# Eddy_ESC.net
KiCad netlist of a schematic drawn in EAGLE
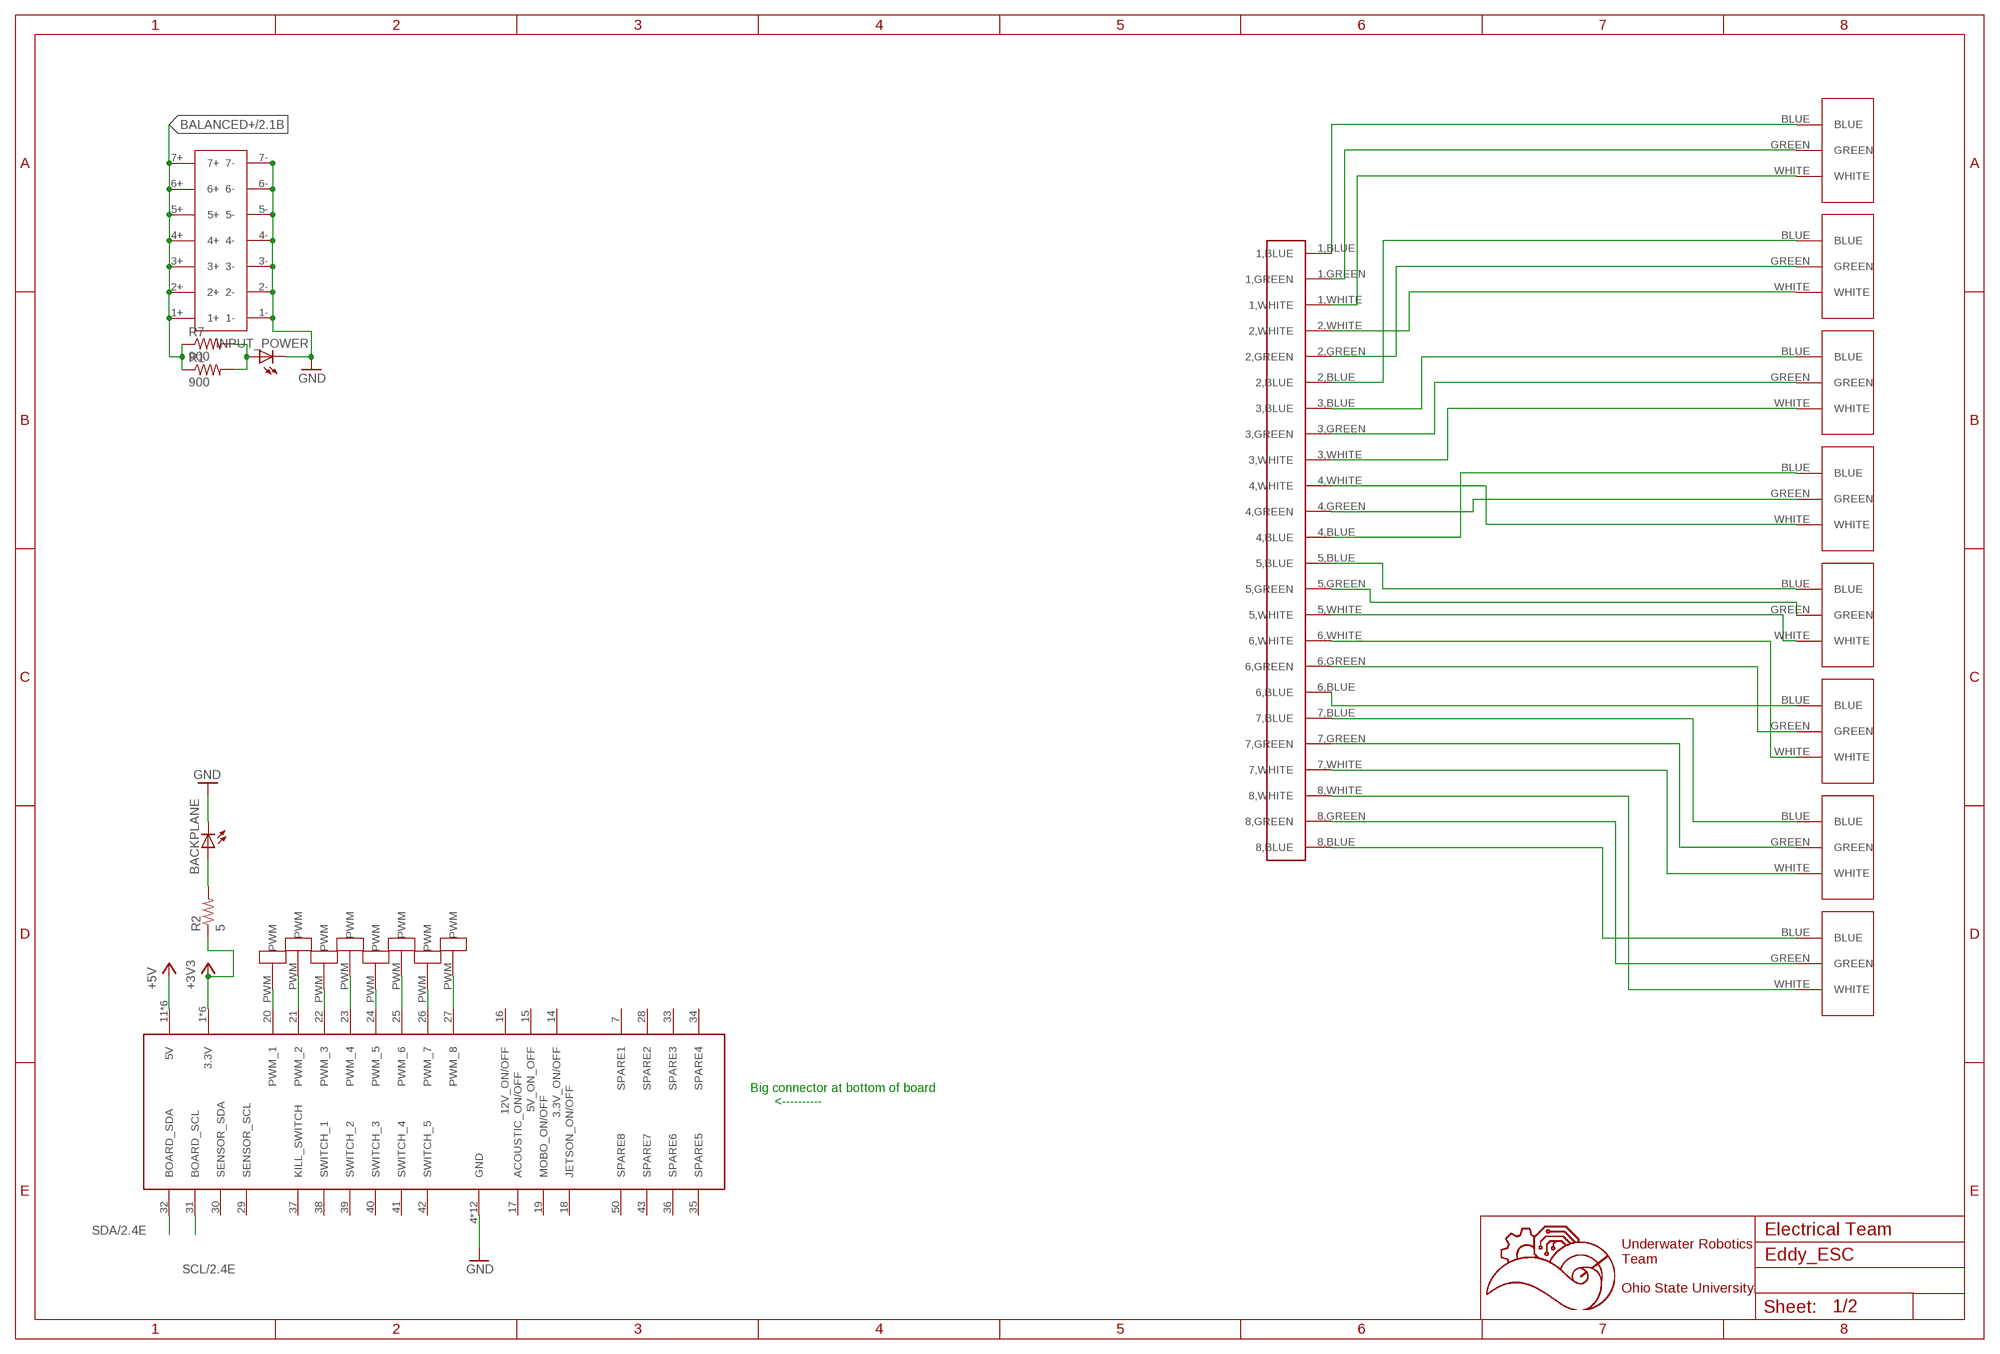
[diagram p0: schematic, sheet 1]
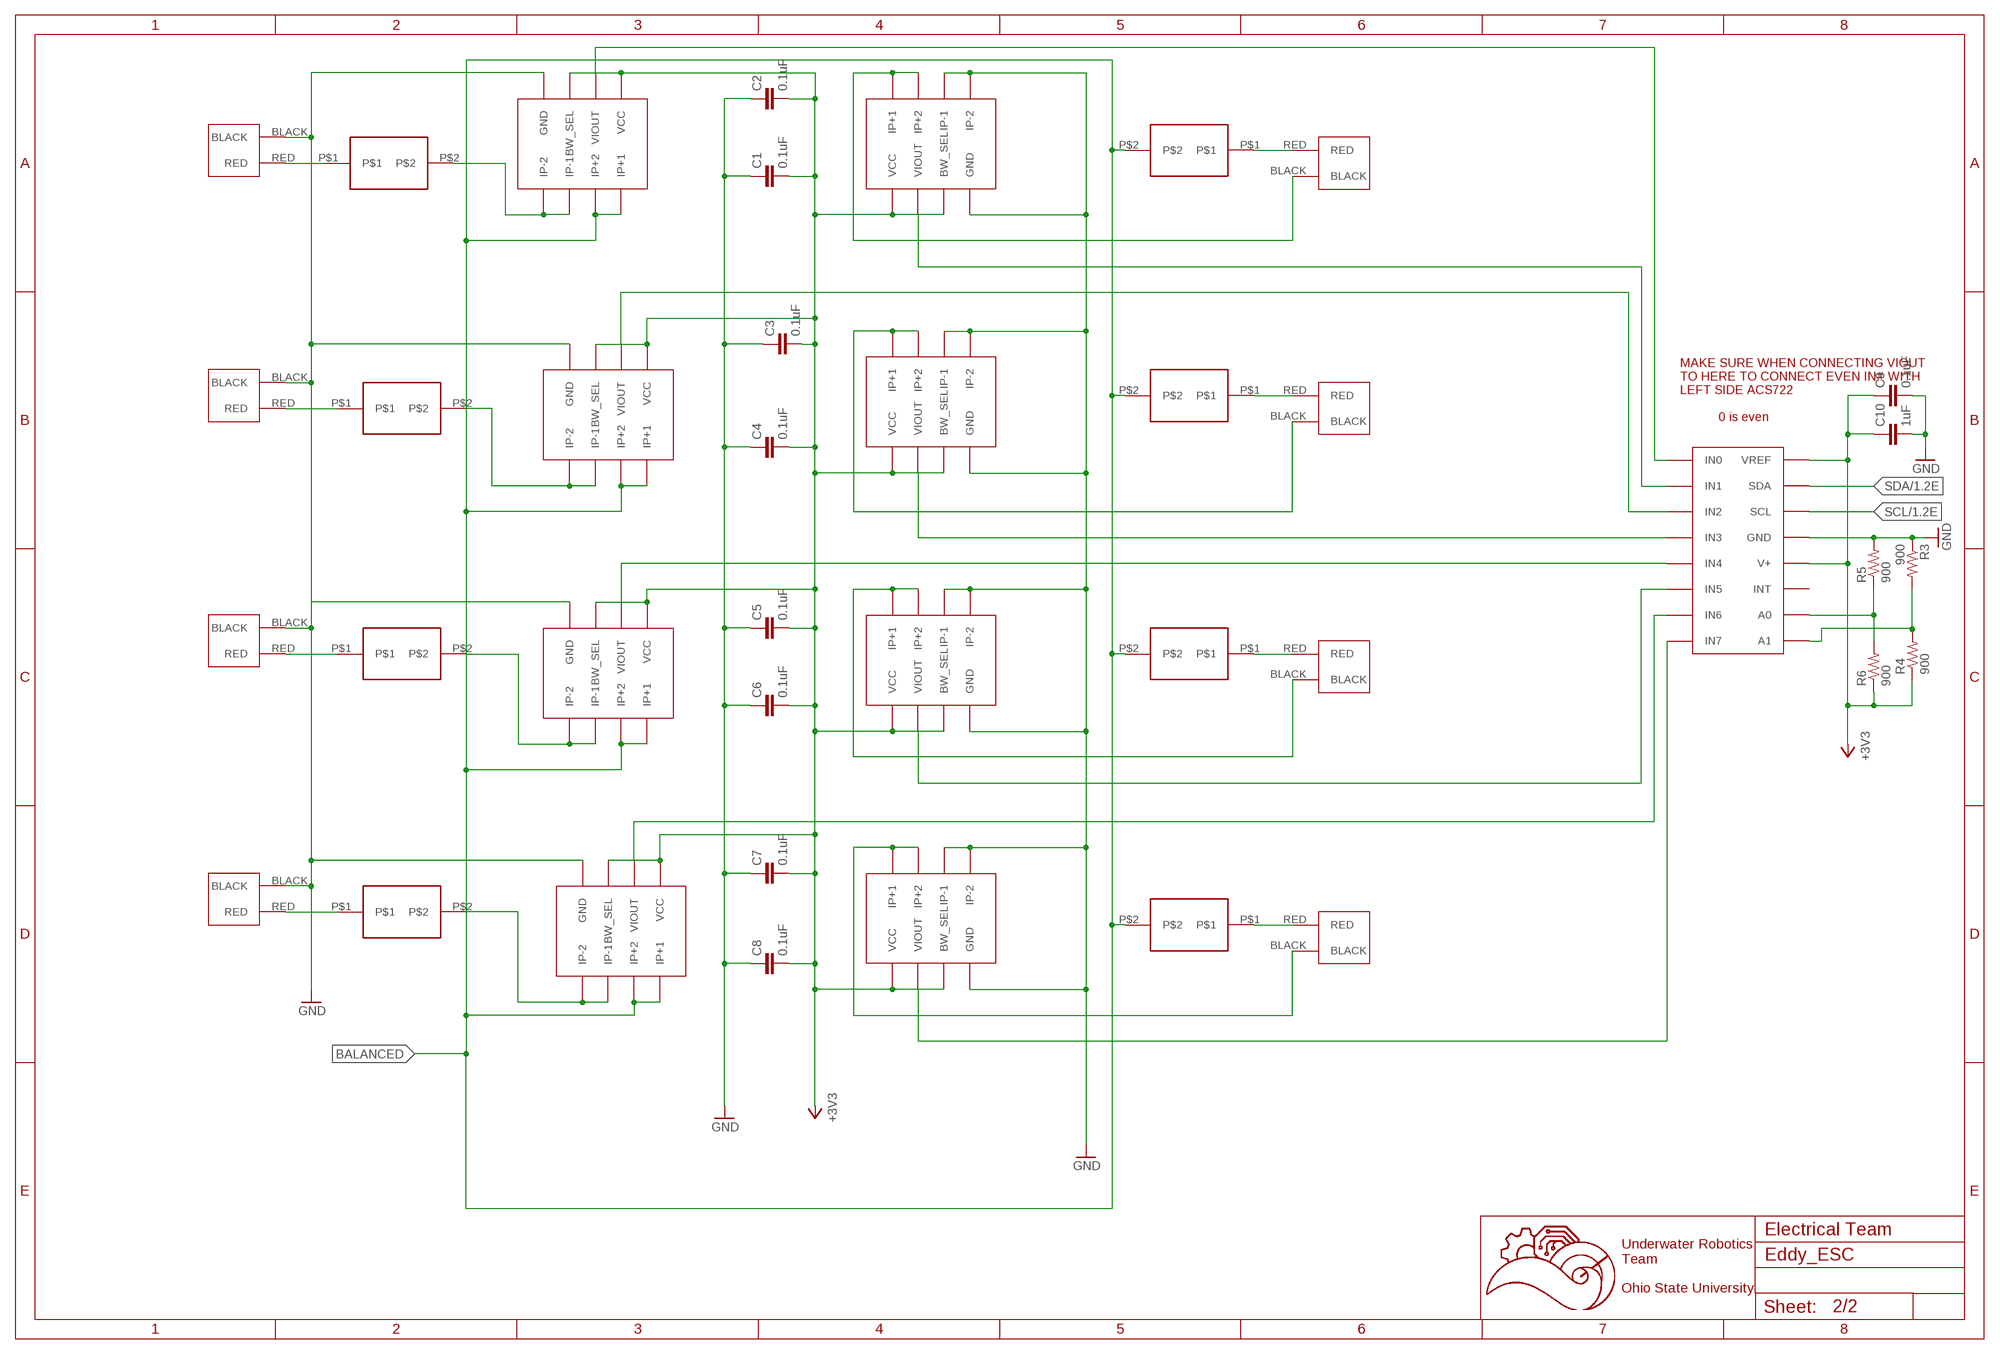
[diagram p1: schematic, sheet 2]

(export (version "E")
  (design (tool "Eeschema 10.0.6"))
  (components
    (comp (ref "C1")
      (value "0.1uF")
      (footprint "eagle-import:C0603")
      (libsource (lib "eagle-import") (part "C-EUC0603"))
    )
    (comp (ref "C2")
      (value "0.1uF")
      (footprint "eagle-import:C0603")
      (libsource (lib "eagle-import") (part "C-EUC0603"))
    )
    (comp (ref "C3")
      (value "0.1uF")
      (footprint "eagle-import:C0603")
      (libsource (lib "eagle-import") (part "C-EUC0603"))
    )
    (comp (ref "C4")
      (value "0.1uF")
      (footprint "eagle-import:C0603")
      (libsource (lib "eagle-import") (part "C-EUC0603"))
    )
    (comp (ref "C5")
      (value "0.1uF")
      (footprint "eagle-import:C0603")
      (libsource (lib "eagle-import") (part "C-EUC0603"))
    )
    (comp (ref "C6")
      (value "0.1uF")
      (footprint "eagle-import:C0603")
      (libsource (lib "eagle-import") (part "C-EUC0603"))
    )
    (comp (ref "C7")
      (value "0.1uF")
      (footprint "eagle-import:C0603")
      (libsource (lib "eagle-import") (part "C-EUC0603"))
    )
    (comp (ref "C8")
      (value "0.1uF")
      (footprint "eagle-import:C0603")
      (libsource (lib "eagle-import") (part "C-EUC0603"))
    )
    (comp (ref "C9")
      (value "0.1uF")
      (footprint "eagle-import:C0603")
      (libsource (lib "eagle-import") (part "C-EUC0603"))
    )
    (comp (ref "C10")
      (value "1uF")
      (footprint "eagle-import:C0603")
      (libsource (lib "eagle-import") (part "C-EUC0603"))
    )
    (comp (ref "R3")
      (value "900")
      (footprint "eagle-import:R0603")
      (libsource (lib "eagle-import") (part "R-US_R0603"))
    )
    (comp (ref "R4")
      (value "900")
      (footprint "eagle-import:R0603")
      (libsource (lib "eagle-import") (part "R-US_R0603"))
    )
    (comp (ref "R5")
      (value "900")
      (footprint "eagle-import:R0603")
      (libsource (lib "eagle-import") (part "R-US_R0603"))
    )
    (comp (ref "R6")
      (value "900")
      (footprint "eagle-import:R0603")
      (libsource (lib "eagle-import") (part "R-US_R0603"))
    )
    (comp (ref "U$20")
      (value "1711725")
      (footprint "eagle-import:1711725")
      (libsource (lib "eagle-import") (part "1711725"))
    )
    (comp (ref "U$21")
      (value "1711725")
      (footprint "eagle-import:1711725")
      (libsource (lib "eagle-import") (part "1711725"))
    )
    (comp (ref "U$22")
      (value "1711725")
      (footprint "eagle-import:1711725")
      (libsource (lib "eagle-import") (part "1711725"))
    )
    (comp (ref "U$23")
      (value "1711725")
      (footprint "eagle-import:1711725")
      (libsource (lib "eagle-import") (part "1711725"))
    )
    (comp (ref "U$24")
      (value "1711725")
      (footprint "eagle-import:1711725")
      (libsource (lib "eagle-import") (part "1711725"))
    )
    (comp (ref "U$25")
      (value "1711725")
      (footprint "eagle-import:1711725")
      (libsource (lib "eagle-import") (part "1711725"))
    )
    (comp (ref "U$26")
      (value "1711725")
      (footprint "eagle-import:1711725")
      (libsource (lib "eagle-import") (part "1711725"))
    )
    (comp (ref "U$27")
      (value "1711725")
      (footprint "eagle-import:1711725")
      (libsource (lib "eagle-import") (part "1711725"))
    )
    (comp (ref "U$28")
      (value "ACS722")
      (footprint "eagle-import:SOIC-8")
      (libsource (lib "eagle-import") (part "ACS722"))
    )
    (comp (ref "U$29")
      (value "ACS722")
      (footprint "eagle-import:SOIC-8")
      (libsource (lib "eagle-import") (part "ACS722"))
    )
    (comp (ref "U$30")
      (value "ACS722")
      (footprint "eagle-import:SOIC-8")
      (libsource (lib "eagle-import") (part "ACS722"))
    )
    (comp (ref "U$31")
      (value "ACS722")
      (footprint "eagle-import:SOIC-8")
      (libsource (lib "eagle-import") (part "ACS722"))
    )
    (comp (ref "U$32")
      (value "ACS722")
      (footprint "eagle-import:SOIC-8")
      (libsource (lib "eagle-import") (part "ACS722"))
    )
    (comp (ref "U$33")
      (value "ACS722")
      (footprint "eagle-import:SOIC-8")
      (libsource (lib "eagle-import") (part "ACS722"))
    )
    (comp (ref "U$34")
      (value "ACS722")
      (footprint "eagle-import:SOIC-8")
      (libsource (lib "eagle-import") (part "ACS722"))
    )
    (comp (ref "U$35")
      (value "ACS722")
      (footprint "eagle-import:SOIC-8")
      (libsource (lib "eagle-import") (part "ACS722"))
    )
    (comp (ref "U$36")
      (value "ADC128D818")
      (footprint "eagle-import:TSSOP-16")
      (libsource (lib "eagle-import") (part "ADC128D818"))
    )
    (comp (ref "U$37")
      (value "1206SFH")
      (footprint "eagle-import:1206SFH")
      (libsource (lib "eagle-import") (part "1206SFH"))
    )
    (comp (ref "U$38")
      (value "1206SFH")
      (footprint "eagle-import:1206SFH")
      (libsource (lib "eagle-import") (part "1206SFH"))
    )
    (comp (ref "U$39")
      (value "1206SFH")
      (footprint "eagle-import:1206SFH")
      (libsource (lib "eagle-import") (part "1206SFH"))
    )
    (comp (ref "U$40")
      (value "1206SFH")
      (footprint "eagle-import:1206SFH")
      (libsource (lib "eagle-import") (part "1206SFH"))
    )
    (comp (ref "U$41")
      (value "1206SFH")
      (footprint "eagle-import:1206SFH")
      (libsource (lib "eagle-import") (part "1206SFH"))
    )
    (comp (ref "U$42")
      (value "1206SFH")
      (footprint "eagle-import:1206SFH")
      (libsource (lib "eagle-import") (part "1206SFH"))
    )
    (comp (ref "U$43")
      (value "1206SFH")
      (footprint "eagle-import:1206SFH")
      (libsource (lib "eagle-import") (part "1206SFH"))
    )
    (comp (ref "U$44")
      (value "1206SFH")
      (footprint "eagle-import:1206SFH")
      (libsource (lib "eagle-import") (part "1206SFH"))
    )
    (comp (ref "BACKPLANE")
      (value "LEDCHIPLED_0603")
      (footprint "eagle-import:CHIPLED_0603")
      (libsource (lib "eagle-import") (part "LEDCHIPLED_0603"))
    )
    (comp (ref "INPUT_POWER")
      (value "LEDCHIPLED_0603")
      (footprint "eagle-import:CHIPLED_0603")
      (libsource (lib "eagle-import") (part "LEDCHIPLED_0603"))
    )
    (comp (ref "R1")
      (value "900")
      (footprint "eagle-import:R0603")
      (libsource (lib "eagle-import") (part "R-US_R0603"))
    )
    (comp (ref "R2")
      (value "5")
      (footprint "eagle-import:R0603")
      (libsource (lib "eagle-import") (part "R-US_R0603"))
    )
    (comp (ref "R7")
      (value "900")
      (footprint "eagle-import:R0603")
      (libsource (lib "eagle-import") (part "R-US_R0603"))
    )
    (comp (ref "U$1")
      (value "5530843-EDGE")
      (footprint "eagle-import:5530843-6-BOARDFINGERS")
      (libsource (lib "eagle-import") (part "5530843-EDGE"))
    )
    (comp (ref "U$2")
      (value "1711738")
      (footprint "eagle-import:1711738")
      (libsource (lib "eagle-import") (part "1711738"))
    )
    (comp (ref "U$3")
      (value "1711738")
      (footprint "eagle-import:1711738")
      (libsource (lib "eagle-import") (part "1711738"))
    )
    (comp (ref "U$4")
      (value "1711738")
      (footprint "eagle-import:1711738")
      (libsource (lib "eagle-import") (part "1711738"))
    )
    (comp (ref "U$5")
      (value "1711738")
      (footprint "eagle-import:1711738")
      (libsource (lib "eagle-import") (part "1711738"))
    )
    (comp (ref "U$6")
      (value "1711738")
      (footprint "eagle-import:1711738")
      (libsource (lib "eagle-import") (part "1711738"))
    )
    (comp (ref "U$7")
      (value "1711738")
      (footprint "eagle-import:1711738")
      (libsource (lib "eagle-import") (part "1711738"))
    )
    (comp (ref "U$8")
      (value "1711738")
      (footprint "eagle-import:1711738")
      (libsource (lib "eagle-import") (part "1711738"))
    )
    (comp (ref "U$9")
      (value "1711738")
      (footprint "eagle-import:1711738")
      (libsource (lib "eagle-import") (part "1711738"))
    )
    (comp (ref "U$10")
      (value "24PINCONVERTER")
      (footprint "eagle-import:24PINCONVERTER")
      (libsource (lib "eagle-import") (part "24PINCONVERTER"))
    )
    (comp (ref "U$11")
      (value "14PIN_VERT")
      (footprint "eagle-import:14PIN_VERT")
      (libsource (lib "eagle-import") (part "14PIN_VERT"))
    )
    (comp (ref "U$12")
      (value "MALE1PINHEADER")
      (footprint "eagle-import:MALE1PINHEADER")
      (libsource (lib "eagle-import") (part "MALE1PINHEADER"))
    )
    (comp (ref "U$13")
      (value "MALE1PINHEADER")
      (footprint "eagle-import:MALE1PINHEADER")
      (libsource (lib "eagle-import") (part "MALE1PINHEADER"))
    )
    (comp (ref "U$14")
      (value "MALE1PINHEADER")
      (footprint "eagle-import:MALE1PINHEADER")
      (libsource (lib "eagle-import") (part "MALE1PINHEADER"))
    )
    (comp (ref "U$15")
      (value "MALE1PINHEADER")
      (footprint "eagle-import:MALE1PINHEADER")
      (libsource (lib "eagle-import") (part "MALE1PINHEADER"))
    )
    (comp (ref "U$16")
      (value "MALE1PINHEADER")
      (footprint "eagle-import:MALE1PINHEADER")
      (libsource (lib "eagle-import") (part "MALE1PINHEADER"))
    )
    (comp (ref "U$17")
      (value "MALE1PINHEADER")
      (footprint "eagle-import:MALE1PINHEADER")
      (libsource (lib "eagle-import") (part "MALE1PINHEADER"))
    )
    (comp (ref "U$18")
      (value "MALE1PINHEADER")
      (footprint "eagle-import:MALE1PINHEADER")
      (libsource (lib "eagle-import") (part "MALE1PINHEADER"))
    )
    (comp (ref "U$19")
      (value "MALE1PINHEADER")
      (footprint "eagle-import:MALE1PINHEADER")
      (libsource (lib "eagle-import") (part "MALE1PINHEADER"))
    )
  )
  (nets
    (net (code "1") (name "+3V3") (class "Default")
      (node (ref "C1") (pin "2") (pinfunction "2_2") (pintype "passive"))
      (node (ref "C10") (pin "1") (pinfunction "1_1") (pintype "passive"))
      (node (ref "C2") (pin "2") (pinfunction "2_2") (pintype "passive"))
      (node (ref "C3") (pin "2") (pinfunction "2_2") (pintype "passive"))
      (node (ref "C4") (pin "2") (pinfunction "2_2") (pintype "passive"))
      (node (ref "C5") (pin "2") (pinfunction "2_2") (pintype "passive"))
      (node (ref "C6") (pin "2") (pinfunction "2_2") (pintype "passive"))
      (node (ref "C7") (pin "2") (pinfunction "2_2") (pintype "passive"))
      (node (ref "C8") (pin "2") (pinfunction "2_2") (pintype "passive"))
      (node (ref "C9") (pin "1") (pinfunction "1_1") (pintype "passive"))
      (node (ref "R2") (pin "1") (pinfunction "1_1") (pintype "passive"))
      (node (ref "R4") (pin "1") (pinfunction "1_1") (pintype "passive"))
      (node (ref "R6") (pin "1") (pinfunction "1_1") (pintype "passive"))
      (node (ref "U$1") (pin "1") (pinfunction "3.3V_1") (pintype "bidirectional"))
      (node (ref "U$1") (pin "2") (pinfunction "3.3V_2") (pintype "bidirectional"))
      (node (ref "U$1") (pin "3") (pinfunction "3.3V_3") (pintype "bidirectional"))
      (node (ref "U$1") (pin "54") (pinfunction "3.3V_54") (pintype "bidirectional"))
      (node (ref "U$1") (pin "55") (pinfunction "3.3V_55") (pintype "bidirectional"))
      (node (ref "U$1") (pin "56") (pinfunction "3.3V_56") (pintype "bidirectional"))
      (node (ref "U$28") (pin "BW_SEL") (pinfunction "BW_SEL_BW_SEL") (pintype "bidirectional"))
      (node (ref "U$28") (pin "VCC") (pinfunction "VCC_VCC") (pintype "bidirectional"))
      (node (ref "U$29") (pin "BW_SEL") (pinfunction "BW_SEL_BW_SEL") (pintype "bidirectional"))
      (node (ref "U$29") (pin "VCC") (pinfunction "VCC_VCC") (pintype "bidirectional"))
      (node (ref "U$30") (pin "BW_SEL") (pinfunction "BW_SEL_BW_SEL") (pintype "bidirectional"))
      (node (ref "U$30") (pin "VCC") (pinfunction "VCC_VCC") (pintype "bidirectional"))
      (node (ref "U$31") (pin "BW_SEL") (pinfunction "BW_SEL_BW_SEL") (pintype "bidirectional"))
      (node (ref "U$31") (pin "VCC") (pinfunction "VCC_VCC") (pintype "bidirectional"))
      (node (ref "U$32") (pin "BW_SEL") (pinfunction "BW_SEL_BW_SEL") (pintype "bidirectional"))
      (node (ref "U$32") (pin "VCC") (pinfunction "VCC_VCC") (pintype "bidirectional"))
      (node (ref "U$33") (pin "BW_SEL") (pinfunction "BW_SEL_BW_SEL") (pintype "bidirectional"))
      (node (ref "U$33") (pin "VCC") (pinfunction "VCC_VCC") (pintype "bidirectional"))
      (node (ref "U$34") (pin "BW_SEL") (pinfunction "BW_SEL_BW_SEL") (pintype "bidirectional"))
      (node (ref "U$34") (pin "VCC") (pinfunction "VCC_VCC") (pintype "bidirectional"))
      (node (ref "U$35") (pin "BW_SEL") (pinfunction "BW_SEL_BW_SEL") (pintype "bidirectional"))
      (node (ref "U$35") (pin "VCC") (pinfunction "VCC_VCC") (pintype "bidirectional"))
      (node (ref "U$36") (pin "V+") (pinfunction "V+_V+") (pintype "bidirectional"))
      (node (ref "U$36") (pin "VREF") (pinfunction "VREF_VREF") (pintype "bidirectional"))
    )
    (net (code "2") (name "+5V") (class "Default")
      (node (ref "U$1") (pin "11") (pinfunction "5V_11") (pintype "bidirectional"))
      (node (ref "U$1") (pin "12") (pinfunction "5V_12") (pintype "bidirectional"))
      (node (ref "U$1") (pin "13") (pinfunction "5V_13") (pintype "bidirectional"))
      (node (ref "U$1") (pin "44") (pinfunction "5V_44") (pintype "bidirectional"))
      (node (ref "U$1") (pin "45") (pinfunction "5V_45") (pintype "bidirectional"))
      (node (ref "U$1") (pin "46") (pinfunction "5V_46") (pintype "bidirectional"))
    )
    (net (code "3") (name "BALANCED") (class "Default")
      (node (ref "U$32") (pin "IP+1") (pinfunction "IP+1_IP+1") (pintype "bidirectional"))
      (node (ref "U$32") (pin "IP+2") (pinfunction "IP+2_IP+2") (pintype "bidirectional"))
      (node (ref "U$33") (pin "IP+1") (pinfunction "IP+1_IP+1") (pintype "bidirectional"))
      (node (ref "U$33") (pin "IP+2") (pinfunction "IP+2_IP+2") (pintype "bidirectional"))
      (node (ref "U$34") (pin "IP+1") (pinfunction "IP+1_IP+1") (pintype "bidirectional"))
      (node (ref "U$34") (pin "IP+2") (pinfunction "IP+2_IP+2") (pintype "bidirectional"))
      (node (ref "U$35") (pin "IP+1") (pinfunction "IP+1_IP+1") (pintype "bidirectional"))
      (node (ref "U$35") (pin "IP+2") (pinfunction "IP+2_IP+2") (pintype "bidirectional"))
      (node (ref "U$41") (pin "P$2") (pinfunction "P$2_P$2") (pintype "bidirectional"))
      (node (ref "U$42") (pin "P$2") (pinfunction "P$2_P$2") (pintype "bidirectional"))
      (node (ref "U$43") (pin "P$2") (pinfunction "P$2_P$2") (pintype "bidirectional"))
      (node (ref "U$44") (pin "P$2") (pinfunction "P$2_P$2") (pintype "bidirectional"))
    )
    (net (code "4") (name "BALANCED+{slash}2.1B") (class "Default")
      (node (ref "R1") (pin "1") (pinfunction "1_1") (pintype "passive"))
      (node (ref "R7") (pin "1") (pinfunction "1_1") (pintype "passive"))
      (node (ref "U$11") (pin "1+") (pinfunction "1+_1+") (pintype "bidirectional"))
      (node (ref "U$11") (pin "2+") (pinfunction "2+_2+") (pintype "bidirectional"))
      (node (ref "U$11") (pin "3+") (pinfunction "3+_3+") (pintype "bidirectional"))
      (node (ref "U$11") (pin "4+") (pinfunction "4+_4+") (pintype "bidirectional"))
      (node (ref "U$11") (pin "5+") (pinfunction "5+_5+") (pintype "bidirectional"))
      (node (ref "U$11") (pin "6+") (pinfunction "6+_6+") (pintype "bidirectional"))
      (node (ref "U$11") (pin "7+") (pinfunction "7+_7+") (pintype "bidirectional"))
    )
    (net (code "5") (name "GND") (class "Default")
      (node (ref "BACKPLANE") (pin "C") (pinfunction "C_C") (pintype "passive"))
      (node (ref "C1") (pin "1") (pinfunction "1_1") (pintype "passive"))
      (node (ref "C10") (pin "2") (pinfunction "2_2") (pintype "passive"))
      (node (ref "C2") (pin "1") (pinfunction "1_1") (pintype "passive"))
      (node (ref "C3") (pin "1") (pinfunction "1_1") (pintype "passive"))
      (node (ref "C4") (pin "1") (pinfunction "1_1") (pintype "passive"))
      (node (ref "C5") (pin "1") (pinfunction "1_1") (pintype "passive"))
      (node (ref "C6") (pin "1") (pinfunction "1_1") (pintype "passive"))
      (node (ref "C7") (pin "1") (pinfunction "1_1") (pintype "passive"))
      (node (ref "C8") (pin "1") (pinfunction "1_1") (pintype "passive"))
      (node (ref "C9") (pin "2") (pinfunction "2_2") (pintype "passive"))
      (node (ref "INPUT_POWER") (pin "C") (pinfunction "C_C") (pintype "passive"))
      (node (ref "R3") (pin "1") (pinfunction "1_1") (pintype "passive"))
      (node (ref "R5") (pin "2") (pinfunction "2_2") (pintype "passive"))
      (node (ref "U$1") (pin "10") (pinfunction "GND_10") (pintype "bidirectional"))
      (node (ref "U$1") (pin "4") (pinfunction "GND_4") (pintype "bidirectional"))
      (node (ref "U$1") (pin "47") (pinfunction "GND_47") (pintype "bidirectional"))
      (node (ref "U$1") (pin "48") (pinfunction "GND_48") (pintype "bidirectional"))
      (node (ref "U$1") (pin "49") (pinfunction "GND_49") (pintype "bidirectional"))
      (node (ref "U$1") (pin "5") (pinfunction "GND_5") (pintype "bidirectional"))
      (node (ref "U$1") (pin "51") (pinfunction "GND_51") (pintype "bidirectional"))
      (node (ref "U$1") (pin "52") (pinfunction "GND_52") (pintype "bidirectional"))
      (node (ref "U$1") (pin "53") (pinfunction "GND_53") (pintype "bidirectional"))
      (node (ref "U$1") (pin "6") (pinfunction "GND_6") (pintype "bidirectional"))
      (node (ref "U$1") (pin "8") (pinfunction "GND_8") (pintype "bidirectional"))
      (node (ref "U$1") (pin "9") (pinfunction "GND_9") (pintype "bidirectional"))
      (node (ref "U$11") (pin "1-") (pinfunction "1-_1-") (pintype "bidirectional"))
      (node (ref "U$11") (pin "2-") (pinfunction "2-_2-") (pintype "bidirectional"))
      (node (ref "U$11") (pin "3-") (pinfunction "3-_3-") (pintype "bidirectional"))
      (node (ref "U$11") (pin "4-") (pinfunction "4-_4-") (pintype "bidirectional"))
      (node (ref "U$11") (pin "5-") (pinfunction "5-_5-") (pintype "bidirectional"))
      (node (ref "U$11") (pin "6-") (pinfunction "6-_6-") (pintype "bidirectional"))
      (node (ref "U$11") (pin "7-") (pinfunction "7-_7-") (pintype "bidirectional"))
      (node (ref "U$24") (pin "BLACK") (pinfunction "BLACK_BLACK") (pintype "bidirectional"))
      (node (ref "U$25") (pin "BLACK") (pinfunction "BLACK_BLACK") (pintype "bidirectional"))
      (node (ref "U$26") (pin "BLACK") (pinfunction "BLACK_BLACK") (pintype "bidirectional"))
      (node (ref "U$27") (pin "BLACK") (pinfunction "BLACK_BLACK") (pintype "bidirectional"))
      (node (ref "U$28") (pin "GND") (pinfunction "GND_GND") (pintype "bidirectional"))
      (node (ref "U$28") (pin "IP-1") (pinfunction "IP-1_IP-1") (pintype "bidirectional"))
      (node (ref "U$28") (pin "IP-2") (pinfunction "IP-2_IP-2") (pintype "bidirectional"))
      (node (ref "U$29") (pin "GND") (pinfunction "GND_GND") (pintype "bidirectional"))
      (node (ref "U$29") (pin "IP-1") (pinfunction "IP-1_IP-1") (pintype "bidirectional"))
      (node (ref "U$29") (pin "IP-2") (pinfunction "IP-2_IP-2") (pintype "bidirectional"))
      (node (ref "U$30") (pin "GND") (pinfunction "GND_GND") (pintype "bidirectional"))
      (node (ref "U$30") (pin "IP-1") (pinfunction "IP-1_IP-1") (pintype "bidirectional"))
      (node (ref "U$30") (pin "IP-2") (pinfunction "IP-2_IP-2") (pintype "bidirectional"))
      (node (ref "U$31") (pin "GND") (pinfunction "GND_GND") (pintype "bidirectional"))
      (node (ref "U$31") (pin "IP-1") (pinfunction "IP-1_IP-1") (pintype "bidirectional"))
      (node (ref "U$31") (pin "IP-2") (pinfunction "IP-2_IP-2") (pintype "bidirectional"))
      (node (ref "U$32") (pin "GND") (pinfunction "GND_GND") (pintype "bidirectional"))
      (node (ref "U$33") (pin "GND") (pinfunction "GND_GND") (pintype "bidirectional"))
      (node (ref "U$34") (pin "GND") (pinfunction "GND_GND") (pintype "bidirectional"))
      (node (ref "U$35") (pin "GND") (pinfunction "GND_GND") (pintype "bidirectional"))
      (node (ref "U$36") (pin "GND") (pinfunction "GND_GND") (pintype "bidirectional"))
    )
    (net (code "6") (name "Net-(BACKPLANE-PadA)") (class "Default")
      (node (ref "BACKPLANE") (pin "A") (pinfunction "A_A") (pintype "passive"))
      (node (ref "R2") (pin "2") (pinfunction "2_2") (pintype "passive"))
    )
    (net (code "7") (name "Net-(INPUT_POWER-PadA)") (class "Default")
      (node (ref "INPUT_POWER") (pin "A") (pinfunction "A_A") (pintype "passive"))
      (node (ref "R1") (pin "2") (pinfunction "2_2") (pintype "passive"))
      (node (ref "R7") (pin "2") (pinfunction "2_2") (pintype "passive"))
    )
    (net (code "8") (name "Net-(R3-Pad2)") (class "Default")
      (node (ref "R3") (pin "2") (pinfunction "2_2") (pintype "passive"))
      (node (ref "R4") (pin "2") (pinfunction "2_2") (pintype "passive"))
      (node (ref "U$36") (pin "A1") (pinfunction "A1_A1") (pintype "bidirectional"))
    )
    (net (code "9") (name "Net-(R5-Pad1)") (class "Default")
      (node (ref "R5") (pin "1") (pinfunction "1_1") (pintype "passive"))
      (node (ref "R6") (pin "2") (pinfunction "2_2") (pintype "passive"))
      (node (ref "U$36") (pin "A0") (pinfunction "A0_A0") (pintype "bidirectional"))
    )
    (net (code "10") (name "Net-(U$1-PWM_1)") (class "Default")
      (node (ref "U$1") (pin "20") (pinfunction "PWM_1_20") (pintype "bidirectional"))
      (node (ref "U$12") (pin "PWM") (pinfunction "PWM_PWM") (pintype "bidirectional"))
    )
    (net (code "11") (name "Net-(U$1-PWM_2)") (class "Default")
      (node (ref "U$1") (pin "21") (pinfunction "PWM_2_21") (pintype "bidirectional"))
      (node (ref "U$13") (pin "PWM") (pinfunction "PWM_PWM") (pintype "bidirectional"))
    )
    (net (code "12") (name "Net-(U$1-PWM_3)") (class "Default")
      (node (ref "U$1") (pin "22") (pinfunction "PWM_3_22") (pintype "bidirectional"))
      (node (ref "U$14") (pin "PWM") (pinfunction "PWM_PWM") (pintype "bidirectional"))
    )
    (net (code "13") (name "Net-(U$1-PWM_4)") (class "Default")
      (node (ref "U$1") (pin "23") (pinfunction "PWM_4_23") (pintype "bidirectional"))
      (node (ref "U$16") (pin "PWM") (pinfunction "PWM_PWM") (pintype "bidirectional"))
    )
    (net (code "14") (name "Net-(U$1-PWM_5)") (class "Default")
      (node (ref "U$1") (pin "24") (pinfunction "PWM_5_24") (pintype "bidirectional"))
      (node (ref "U$15") (pin "PWM") (pinfunction "PWM_PWM") (pintype "bidirectional"))
    )
    (net (code "15") (name "Net-(U$1-PWM_6)") (class "Default")
      (node (ref "U$1") (pin "25") (pinfunction "PWM_6_25") (pintype "bidirectional"))
      (node (ref "U$17") (pin "PWM") (pinfunction "PWM_PWM") (pintype "bidirectional"))
    )
    (net (code "16") (name "Net-(U$1-PWM_7)") (class "Default")
      (node (ref "U$1") (pin "26") (pinfunction "PWM_7_26") (pintype "bidirectional"))
      (node (ref "U$18") (pin "PWM") (pinfunction "PWM_PWM") (pintype "bidirectional"))
    )
    (net (code "17") (name "Net-(U$1-PWM_8)") (class "Default")
      (node (ref "U$1") (pin "27") (pinfunction "PWM_8_27") (pintype "bidirectional"))
      (node (ref "U$19") (pin "PWM") (pinfunction "PWM_PWM") (pintype "bidirectional"))
    )
    (net (code "18") (name "Net-(U$10-Pad1,BLUE)") (class "Default")
      (node (ref "U$10") (pin "1,BLUE") (pinfunction "1,BLUE_1,BLUE") (pintype "bidirectional"))
      (node (ref "U$9") (pin "BLUE") (pinfunction "BLUE_BLUE") (pintype "bidirectional"))
    )
    (net (code "19") (name "Net-(U$10-Pad1,GREEN)") (class "Default")
      (node (ref "U$10") (pin "1,GREEN") (pinfunction "1,GREEN_1,GREEN") (pintype "bidirectional"))
      (node (ref "U$9") (pin "GREEN") (pinfunction "GREEN_GREEN") (pintype "bidirectional"))
    )
    (net (code "20") (name "Net-(U$10-Pad1,WHITE)") (class "Default")
      (node (ref "U$10") (pin "1,WHITE") (pinfunction "1,WHITE_1,WHITE") (pintype "bidirectional"))
      (node (ref "U$9") (pin "WHITE") (pinfunction "WHITE_WHITE") (pintype "bidirectional"))
    )
    (net (code "21") (name "Net-(U$10-Pad2,BLUE)") (class "Default")
      (node (ref "U$10") (pin "2,BLUE") (pinfunction "2,BLUE_2,BLUE") (pintype "bidirectional"))
      (node (ref "U$2") (pin "BLUE") (pinfunction "BLUE_BLUE") (pintype "bidirectional"))
    )
    (net (code "22") (name "Net-(U$10-Pad2,GREEN)") (class "Default")
      (node (ref "U$10") (pin "2,GREEN") (pinfunction "2,GREEN_2,GREEN") (pintype "bidirectional"))
      (node (ref "U$2") (pin "GREEN") (pinfunction "GREEN_GREEN") (pintype "bidirectional"))
    )
    (net (code "23") (name "Net-(U$10-Pad2,WHITE)") (class "Default")
      (node (ref "U$10") (pin "2,WHITE") (pinfunction "2,WHITE_2,WHITE") (pintype "bidirectional"))
      (node (ref "U$2") (pin "WHITE") (pinfunction "WHITE_WHITE") (pintype "bidirectional"))
    )
    (net (code "24") (name "Net-(U$10-Pad3,BLUE)") (class "Default")
      (node (ref "U$10") (pin "3,BLUE") (pinfunction "3,BLUE_3,BLUE") (pintype "bidirectional"))
      (node (ref "U$3") (pin "BLUE") (pinfunction "BLUE_BLUE") (pintype "bidirectional"))
    )
    (net (code "25") (name "Net-(U$10-Pad3,GREEN)") (class "Default")
      (node (ref "U$10") (pin "3,GREEN") (pinfunction "3,GREEN_3,GREEN") (pintype "bidirectional"))
      (node (ref "U$3") (pin "GREEN") (pinfunction "GREEN_GREEN") (pintype "bidirectional"))
    )
    (net (code "26") (name "Net-(U$10-Pad3,WHITE)") (class "Default")
      (node (ref "U$10") (pin "3,WHITE") (pinfunction "3,WHITE_3,WHITE") (pintype "bidirectional"))
      (node (ref "U$3") (pin "WHITE") (pinfunction "WHITE_WHITE") (pintype "bidirectional"))
    )
    (net (code "27") (name "Net-(U$10-Pad4,BLUE)") (class "Default")
      (node (ref "U$10") (pin "4,BLUE") (pinfunction "4,BLUE_4,BLUE") (pintype "bidirectional"))
      (node (ref "U$4") (pin "BLUE") (pinfunction "BLUE_BLUE") (pintype "bidirectional"))
    )
    (net (code "28") (name "Net-(U$10-Pad4,GREEN)") (class "Default")
      (node (ref "U$10") (pin "4,GREEN") (pinfunction "4,GREEN_4,GREEN") (pintype "bidirectional"))
      (node (ref "U$4") (pin "GREEN") (pinfunction "GREEN_GREEN") (pintype "bidirectional"))
    )
    (net (code "29") (name "Net-(U$10-Pad4,WHITE)") (class "Default")
      (node (ref "U$10") (pin "4,WHITE") (pinfunction "4,WHITE_4,WHITE") (pintype "bidirectional"))
      (node (ref "U$4") (pin "WHITE") (pinfunction "WHITE_WHITE") (pintype "bidirectional"))
    )
    (net (code "30") (name "Net-(U$10-Pad5,BLUE)") (class "Default")
      (node (ref "U$10") (pin "5,BLUE") (pinfunction "5,BLUE_5,BLUE") (pintype "bidirectional"))
      (node (ref "U$5") (pin "BLUE") (pinfunction "BLUE_BLUE") (pintype "bidirectional"))
    )
    (net (code "31") (name "Net-(U$10-Pad5,GREEN)") (class "Default")
      (node (ref "U$10") (pin "5,GREEN") (pinfunction "5,GREEN_5,GREEN") (pintype "bidirectional"))
      (node (ref "U$5") (pin "GREEN") (pinfunction "GREEN_GREEN") (pintype "bidirectional"))
    )
    (net (code "32") (name "Net-(U$10-Pad5,WHITE)") (class "Default")
      (node (ref "U$10") (pin "5,WHITE") (pinfunction "5,WHITE_5,WHITE") (pintype "bidirectional"))
      (node (ref "U$5") (pin "WHITE") (pinfunction "WHITE_WHITE") (pintype "bidirectional"))
    )
    (net (code "33") (name "Net-(U$10-Pad6,BLUE)") (class "Default")
      (node (ref "U$10") (pin "6,BLUE") (pinfunction "6,BLUE_6,BLUE") (pintype "bidirectional"))
      (node (ref "U$6") (pin "BLUE") (pinfunction "BLUE_BLUE") (pintype "bidirectional"))
    )
    (net (code "34") (name "Net-(U$10-Pad6,GREEN)") (class "Default")
      (node (ref "U$10") (pin "6,GREEN") (pinfunction "6,GREEN_6,GREEN") (pintype "bidirectional"))
      (node (ref "U$6") (pin "GREEN") (pinfunction "GREEN_GREEN") (pintype "bidirectional"))
    )
    (net (code "35") (name "Net-(U$10-Pad6,WHITE)") (class "Default")
      (node (ref "U$10") (pin "6,WHITE") (pinfunction "6,WHITE_6,WHITE") (pintype "bidirectional"))
      (node (ref "U$6") (pin "WHITE") (pinfunction "WHITE_WHITE") (pintype "bidirectional"))
    )
    (net (code "36") (name "Net-(U$10-Pad7,BLUE)") (class "Default")
      (node (ref "U$10") (pin "7,BLUE") (pinfunction "7,BLUE_7,BLUE") (pintype "bidirectional"))
      (node (ref "U$7") (pin "BLUE") (pinfunction "BLUE_BLUE") (pintype "bidirectional"))
    )
    (net (code "37") (name "Net-(U$10-Pad7,GREEN)") (class "Default")
      (node (ref "U$10") (pin "7,GREEN") (pinfunction "7,GREEN_7,GREEN") (pintype "bidirectional"))
      (node (ref "U$7") (pin "GREEN") (pinfunction "GREEN_GREEN") (pintype "bidirectional"))
    )
    (net (code "38") (name "Net-(U$10-Pad7,WHITE)") (class "Default")
      (node (ref "U$10") (pin "7,WHITE") (pinfunction "7,WHITE_7,WHITE") (pintype "bidirectional"))
      (node (ref "U$7") (pin "WHITE") (pinfunction "WHITE_WHITE") (pintype "bidirectional"))
    )
    (net (code "39") (name "Net-(U$10-Pad8,BLUE)") (class "Default")
      (node (ref "U$10") (pin "8,BLUE") (pinfunction "8,BLUE_8,BLUE") (pintype "bidirectional"))
      (node (ref "U$8") (pin "BLUE") (pinfunction "BLUE_BLUE") (pintype "bidirectional"))
    )
    (net (code "40") (name "Net-(U$10-Pad8,GREEN)") (class "Default")
      (node (ref "U$10") (pin "8,GREEN") (pinfunction "8,GREEN_8,GREEN") (pintype "bidirectional"))
      (node (ref "U$8") (pin "GREEN") (pinfunction "GREEN_GREEN") (pintype "bidirectional"))
    )
    (net (code "41") (name "Net-(U$10-Pad8,WHITE)") (class "Default")
      (node (ref "U$10") (pin "8,WHITE") (pinfunction "8,WHITE_8,WHITE") (pintype "bidirectional"))
      (node (ref "U$8") (pin "WHITE") (pinfunction "WHITE_WHITE") (pintype "bidirectional"))
    )
    (net (code "42") (name "Net-(U$20-PadBLACK)") (class "Default")
      (node (ref "U$20") (pin "BLACK") (pinfunction "BLACK_BLACK") (pintype "bidirectional"))
      (node (ref "U$28") (pin "IP+1") (pinfunction "IP+1_IP+1") (pintype "bidirectional"))
      (node (ref "U$28") (pin "IP+2") (pinfunction "IP+2_IP+2") (pintype "bidirectional"))
    )
    (net (code "43") (name "Net-(U$20-PadRED)") (class "Default")
      (node (ref "U$20") (pin "RED") (pinfunction "RED_RED") (pintype "bidirectional"))
      (node (ref "U$41") (pin "P$1") (pinfunction "P$1_P$1") (pintype "bidirectional"))
    )
    (net (code "44") (name "Net-(U$21-PadBLACK)") (class "Default")
      (node (ref "U$21") (pin "BLACK") (pinfunction "BLACK_BLACK") (pintype "bidirectional"))
      (node (ref "U$29") (pin "IP+1") (pinfunction "IP+1_IP+1") (pintype "bidirectional"))
      (node (ref "U$29") (pin "IP+2") (pinfunction "IP+2_IP+2") (pintype "bidirectional"))
    )
    (net (code "45") (name "Net-(U$21-PadRED)") (class "Default")
      (node (ref "U$21") (pin "RED") (pinfunction "RED_RED") (pintype "bidirectional"))
      (node (ref "U$42") (pin "P$1") (pinfunction "P$1_P$1") (pintype "bidirectional"))
    )
    (net (code "46") (name "Net-(U$22-PadBLACK)") (class "Default")
      (node (ref "U$22") (pin "BLACK") (pinfunction "BLACK_BLACK") (pintype "bidirectional"))
      (node (ref "U$30") (pin "IP+1") (pinfunction "IP+1_IP+1") (pintype "bidirectional"))
      (node (ref "U$30") (pin "IP+2") (pinfunction "IP+2_IP+2") (pintype "bidirectional"))
    )
    (net (code "47") (name "Net-(U$22-PadRED)") (class "Default")
      (node (ref "U$22") (pin "RED") (pinfunction "RED_RED") (pintype "bidirectional"))
      (node (ref "U$43") (pin "P$1") (pinfunction "P$1_P$1") (pintype "bidirectional"))
    )
    (net (code "48") (name "Net-(U$23-PadBLACK)") (class "Default")
      (node (ref "U$23") (pin "BLACK") (pinfunction "BLACK_BLACK") (pintype "bidirectional"))
      (node (ref "U$31") (pin "IP+1") (pinfunction "IP+1_IP+1") (pintype "bidirectional"))
      (node (ref "U$31") (pin "IP+2") (pinfunction "IP+2_IP+2") (pintype "bidirectional"))
    )
    (net (code "49") (name "Net-(U$23-PadRED)") (class "Default")
      (node (ref "U$23") (pin "RED") (pinfunction "RED_RED") (pintype "bidirectional"))
      (node (ref "U$44") (pin "P$1") (pinfunction "P$1_P$1") (pintype "bidirectional"))
    )
    (net (code "50") (name "Net-(U$24-PadRED)") (class "Default")
      (node (ref "U$24") (pin "RED") (pinfunction "RED_RED") (pintype "bidirectional"))
      (node (ref "U$37") (pin "P$1") (pinfunction "P$1_P$1") (pintype "bidirectional"))
    )
    (net (code "51") (name "Net-(U$25-PadRED)") (class "Default")
      (node (ref "U$25") (pin "RED") (pinfunction "RED_RED") (pintype "bidirectional"))
      (node (ref "U$38") (pin "P$1") (pinfunction "P$1_P$1") (pintype "bidirectional"))
    )
    (net (code "52") (name "Net-(U$26-PadRED)") (class "Default")
      (node (ref "U$26") (pin "RED") (pinfunction "RED_RED") (pintype "bidirectional"))
      (node (ref "U$39") (pin "P$1") (pinfunction "P$1_P$1") (pintype "bidirectional"))
    )
    (net (code "53") (name "Net-(U$27-PadRED)") (class "Default")
      (node (ref "U$27") (pin "RED") (pinfunction "RED_RED") (pintype "bidirectional"))
      (node (ref "U$40") (pin "P$1") (pinfunction "P$1_P$1") (pintype "bidirectional"))
    )
    (net (code "54") (name "Net-(U$28-PadVIOUT)") (class "Default")
      (node (ref "U$28") (pin "VIOUT") (pinfunction "VIOUT_VIOUT") (pintype "bidirectional"))
      (node (ref "U$36") (pin "IN1") (pinfunction "IN1_IN1") (pintype "bidirectional"))
    )
    (net (code "55") (name "Net-(U$29-PadVIOUT)") (class "Default")
      (node (ref "U$29") (pin "VIOUT") (pinfunction "VIOUT_VIOUT") (pintype "bidirectional"))
      (node (ref "U$36") (pin "IN3") (pinfunction "IN3_IN3") (pintype "bidirectional"))
    )
    (net (code "56") (name "Net-(U$30-PadVIOUT)") (class "Default")
      (node (ref "U$30") (pin "VIOUT") (pinfunction "VIOUT_VIOUT") (pintype "bidirectional"))
      (node (ref "U$36") (pin "IN5") (pinfunction "IN5_IN5") (pintype "bidirectional"))
    )
    (net (code "57") (name "Net-(U$31-PadVIOUT)") (class "Default")
      (node (ref "U$31") (pin "VIOUT") (pinfunction "VIOUT_VIOUT") (pintype "bidirectional"))
      (node (ref "U$36") (pin "IN7") (pinfunction "IN7_IN7") (pintype "bidirectional"))
    )
    (net (code "58") (name "Net-(U$32-PadIP-1)") (class "Default")
      (node (ref "U$32") (pin "IP-1") (pinfunction "IP-1_IP-1") (pintype "bidirectional"))
      (node (ref "U$32") (pin "IP-2") (pinfunction "IP-2_IP-2") (pintype "bidirectional"))
      (node (ref "U$37") (pin "P$2") (pinfunction "P$2_P$2") (pintype "bidirectional"))
    )
    (net (code "59") (name "Net-(U$32-PadVIOUT)") (class "Default")
      (node (ref "U$32") (pin "VIOUT") (pinfunction "VIOUT_VIOUT") (pintype "bidirectional"))
      (node (ref "U$36") (pin "IN0") (pinfunction "IN0_IN0") (pintype "bidirectional"))
    )
    (net (code "60") (name "Net-(U$33-PadIP-1)") (class "Default")
      (node (ref "U$33") (pin "IP-1") (pinfunction "IP-1_IP-1") (pintype "bidirectional"))
      (node (ref "U$33") (pin "IP-2") (pinfunction "IP-2_IP-2") (pintype "bidirectional"))
      (node (ref "U$38") (pin "P$2") (pinfunction "P$2_P$2") (pintype "bidirectional"))
    )
    (net (code "61") (name "Net-(U$33-PadVIOUT)") (class "Default")
      (node (ref "U$33") (pin "VIOUT") (pinfunction "VIOUT_VIOUT") (pintype "bidirectional"))
      (node (ref "U$36") (pin "IN2") (pinfunction "IN2_IN2") (pintype "bidirectional"))
    )
    (net (code "62") (name "Net-(U$34-PadIP-1)") (class "Default")
      (node (ref "U$34") (pin "IP-1") (pinfunction "IP-1_IP-1") (pintype "bidirectional"))
      (node (ref "U$34") (pin "IP-2") (pinfunction "IP-2_IP-2") (pintype "bidirectional"))
      (node (ref "U$39") (pin "P$2") (pinfunction "P$2_P$2") (pintype "bidirectional"))
    )
    (net (code "63") (name "Net-(U$34-PadVIOUT)") (class "Default")
      (node (ref "U$34") (pin "VIOUT") (pinfunction "VIOUT_VIOUT") (pintype "bidirectional"))
      (node (ref "U$36") (pin "IN4") (pinfunction "IN4_IN4") (pintype "bidirectional"))
    )
    (net (code "64") (name "Net-(U$35-PadIP-1)") (class "Default")
      (node (ref "U$35") (pin "IP-1") (pinfunction "IP-1_IP-1") (pintype "bidirectional"))
      (node (ref "U$35") (pin "IP-2") (pinfunction "IP-2_IP-2") (pintype "bidirectional"))
      (node (ref "U$40") (pin "P$2") (pinfunction "P$2_P$2") (pintype "bidirectional"))
    )
    (net (code "65") (name "Net-(U$35-PadVIOUT)") (class "Default")
      (node (ref "U$35") (pin "VIOUT") (pinfunction "VIOUT_VIOUT") (pintype "bidirectional"))
      (node (ref "U$36") (pin "IN6") (pinfunction "IN6_IN6") (pintype "bidirectional"))
    )
    (net (code "66") (name "SCL{slash}1.2E") (class "Default")
      (node (ref "U$36") (pin "SCL") (pinfunction "SCL_SCL") (pintype "bidirectional"))
    )
    (net (code "67") (name "SCL{slash}2.4E") (class "Default")
      (node (ref "U$1") (pin "31") (pinfunction "BOARD_SCL_31") (pintype "bidirectional"))
    )
    (net (code "68") (name "SDA{slash}1.2E") (class "Default")
      (node (ref "U$36") (pin "SDA") (pinfunction "SDA_SDA") (pintype "bidirectional"))
    )
    (net (code "69") (name "SDA{slash}2.4E") (class "Default")
      (node (ref "U$1") (pin "32") (pinfunction "BOARD_SDA_32") (pintype "bidirectional"))
    )
    (net (code "70") (name "unconnected-(U$1-3.3V_ON{slash}OFF-Pad14)") (class "Default")
      (node (ref "U$1") (pin "14") (pinfunction "3.3V_ON/OFF_14") (pintype "bidirectional"))
    )
    (net (code "71") (name "unconnected-(U$1-5V_ON_OFF-Pad15)") (class "Default")
      (node (ref "U$1") (pin "15") (pinfunction "5V_ON_OFF_15") (pintype "bidirectional"))
    )
    (net (code "72") (name "unconnected-(U$1-12V_ON{slash}OFF-Pad16)") (class "Default")
      (node (ref "U$1") (pin "16") (pinfunction "12V_ON/OFF_16") (pintype "bidirectional"))
    )
    (net (code "73") (name "unconnected-(U$1-ACOUSTIC_ON{slash}OFF-Pad17)") (class "Default")
      (node (ref "U$1") (pin "17") (pinfunction "ACOUSTIC_ON/OFF_17") (pintype "bidirectional"))
    )
    (net (code "74") (name "unconnected-(U$1-JETSON_ON{slash}OFF-Pad18)") (class "Default")
      (node (ref "U$1") (pin "18") (pinfunction "JETSON_ON/OFF_18") (pintype "bidirectional"))
    )
    (net (code "75") (name "unconnected-(U$1-KILL_SWITCH-Pad37)") (class "Default")
      (node (ref "U$1") (pin "37") (pinfunction "KILL_SWITCH_37") (pintype "output"))
    )
    (net (code "76") (name "unconnected-(U$1-MOBO_ON{slash}OFF-Pad19)") (class "Default")
      (node (ref "U$1") (pin "19") (pinfunction "MOBO_ON/OFF_19") (pintype "bidirectional"))
    )
    (net (code "77") (name "unconnected-(U$1-SENSOR_SCL-Pad29)") (class "Default")
      (node (ref "U$1") (pin "29") (pinfunction "SENSOR_SCL_29") (pintype "bidirectional"))
    )
    (net (code "78") (name "unconnected-(U$1-SENSOR_SDA-Pad30)") (class "Default")
      (node (ref "U$1") (pin "30") (pinfunction "SENSOR_SDA_30") (pintype "bidirectional"))
    )
    (net (code "79") (name "unconnected-(U$1-SPARE1-Pad7)") (class "Default")
      (node (ref "U$1") (pin "7") (pinfunction "SPARE1_7") (pintype "bidirectional"))
    )
    (net (code "80") (name "unconnected-(U$1-SPARE2-Pad28)") (class "Default")
      (node (ref "U$1") (pin "28") (pinfunction "SPARE2_28") (pintype "bidirectional"))
    )
    (net (code "81") (name "unconnected-(U$1-SPARE3-Pad33)") (class "Default")
      (node (ref "U$1") (pin "33") (pinfunction "SPARE3_33") (pintype "bidirectional"))
    )
    (net (code "82") (name "unconnected-(U$1-SPARE4-Pad34)") (class "Default")
      (node (ref "U$1") (pin "34") (pinfunction "SPARE4_34") (pintype "bidirectional"))
    )
    (net (code "83") (name "unconnected-(U$1-SPARE5-Pad35)") (class "Default")
      (node (ref "U$1") (pin "35") (pinfunction "SPARE5_35") (pintype "bidirectional"))
    )
    (net (code "84") (name "unconnected-(U$1-SPARE6-Pad36)") (class "Default")
      (node (ref "U$1") (pin "36") (pinfunction "SPARE6_36") (pintype "bidirectional"))
    )
    (net (code "85") (name "unconnected-(U$1-SPARE7-Pad43)") (class "Default")
      (node (ref "U$1") (pin "43") (pinfunction "SPARE7_43") (pintype "bidirectional"))
    )
    (net (code "86") (name "unconnected-(U$1-SPARE8-Pad50)") (class "Default")
      (node (ref "U$1") (pin "50") (pinfunction "SPARE8_50") (pintype "bidirectional"))
    )
    (net (code "87") (name "unconnected-(U$1-SWITCH_1-Pad38)") (class "Default")
      (node (ref "U$1") (pin "38") (pinfunction "SWITCH_1_38") (pintype "output"))
    )
    (net (code "88") (name "unconnected-(U$1-SWITCH_2-Pad39)") (class "Default")
      (node (ref "U$1") (pin "39") (pinfunction "SWITCH_2_39") (pintype "output"))
    )
    (net (code "89") (name "unconnected-(U$1-SWITCH_3-Pad40)") (class "Default")
      (node (ref "U$1") (pin "40") (pinfunction "SWITCH_3_40") (pintype "output"))
    )
    (net (code "90") (name "unconnected-(U$1-SWITCH_4-Pad41)") (class "Default")
      (node (ref "U$1") (pin "41") (pinfunction "SWITCH_4_41") (pintype "output"))
    )
    (net (code "91") (name "unconnected-(U$1-SWITCH_5-Pad42)") (class "Default")
      (node (ref "U$1") (pin "42") (pinfunction "SWITCH_5_42") (pintype "output"))
    )
    (net (code "92") (name "unconnected-(U$36-PadINT)") (class "Default")
      (node (ref "U$36") (pin "INT") (pinfunction "INT_INT") (pintype "bidirectional"))
    )
  )
)
